# PEACM1.net
KiCad netlist of a schematic drawn in EAGLE
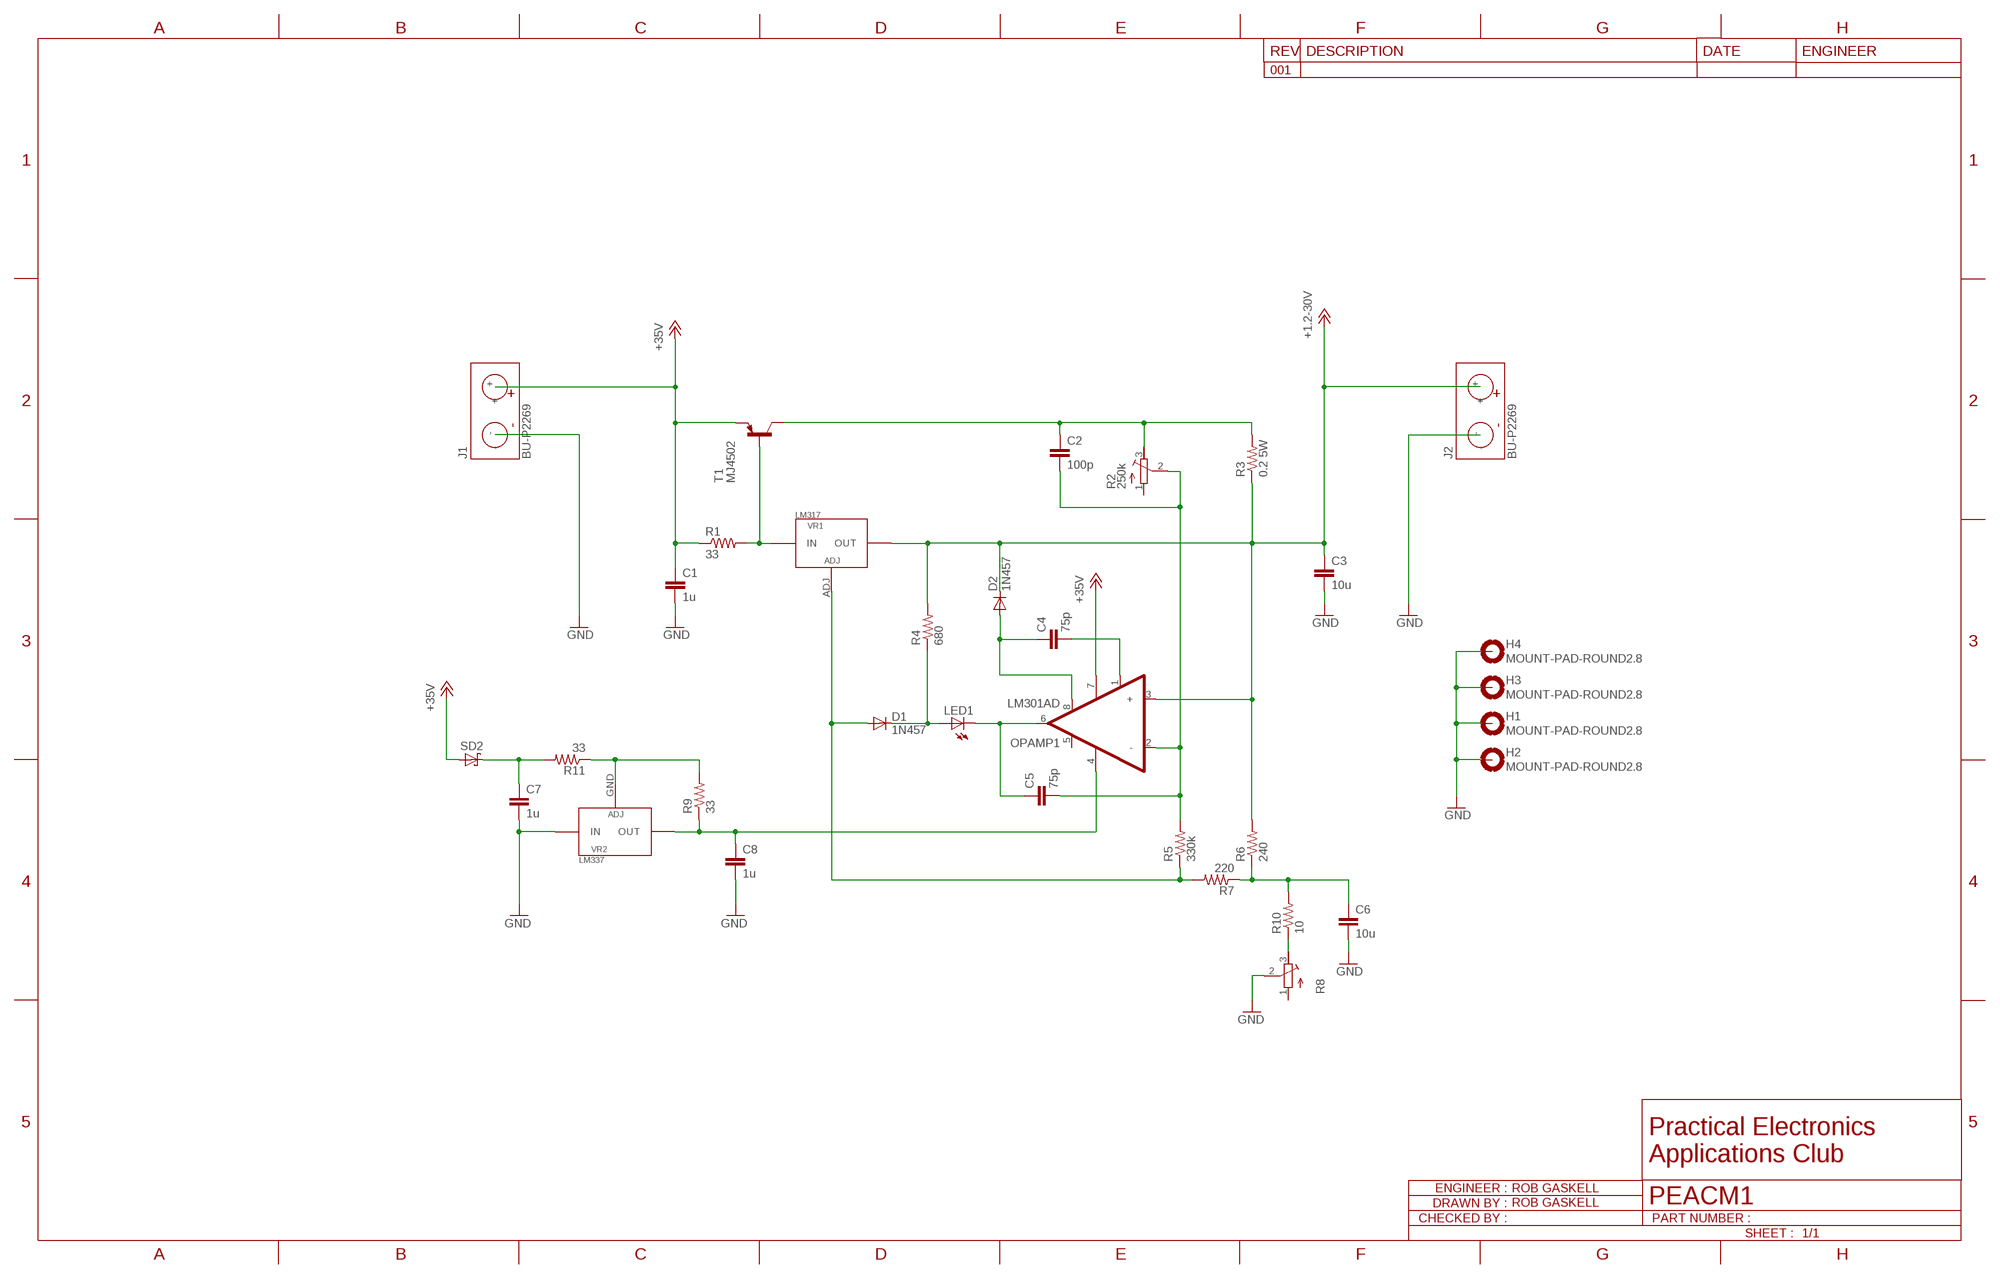
[diagram p0: schematic, sheet 1]

(export (version "E")
  (design (tool "Eeschema 10.0.6"))
  (components
    (comp (ref "C1")
      (value "1u")
      (footprint "eagle-import:C0805")
      (libsource (lib "eagle-import") (part "C-EUC0805"))
    )
    (comp (ref "C2")
      (value "100p")
      (footprint "eagle-import:C0805")
      (libsource (lib "eagle-import") (part "C-EUC0805"))
    )
    (comp (ref "C3")
      (value "10u")
      (footprint "eagle-import:C0805")
      (libsource (lib "eagle-import") (part "C-EUC0805"))
    )
    (comp (ref "C4")
      (value "75p")
      (footprint "eagle-import:C0805")
      (libsource (lib "eagle-import") (part "C-EUC0805"))
    )
    (comp (ref "C5")
      (value "75p")
      (footprint "eagle-import:C0805")
      (libsource (lib "eagle-import") (part "C-EUC0805"))
    )
    (comp (ref "C6")
      (value "10u")
      (footprint "eagle-import:C0805")
      (libsource (lib "eagle-import") (part "C-EUC0805"))
    )
    (comp (ref "C7")
      (value "1u")
      (footprint "eagle-import:C0805")
      (libsource (lib "eagle-import") (part "C-EUC0805"))
    )
    (comp (ref "C8")
      (value "1u")
      (footprint "eagle-import:C0805")
      (libsource (lib "eagle-import") (part "C-EUC0805"))
    )
    (comp (ref "D1")
      (value "1N457")
      (footprint "eagle-import:DO35-10")
      (libsource (lib "eagle-import") (part "DIODE-DO35-10"))
    )
    (comp (ref "D2")
      (value "1N457")
      (footprint "eagle-import:DO35-10")
      (libsource (lib "eagle-import") (part "DIODE-DO35-10"))
    )
    (comp (ref "H1")
      (value "MOUNT-PAD-ROUND2.8")
      (footprint "eagle-import:2,8-PAD")
      (libsource (lib "eagle-import") (part "MOUNT-PAD-ROUND2.8"))
    )
    (comp (ref "H2")
      (value "MOUNT-PAD-ROUND2.8")
      (footprint "eagle-import:2,8-PAD")
      (libsource (lib "eagle-import") (part "MOUNT-PAD-ROUND2.8"))
    )
    (comp (ref "H3")
      (value "MOUNT-PAD-ROUND2.8")
      (footprint "eagle-import:2,8-PAD")
      (libsource (lib "eagle-import") (part "MOUNT-PAD-ROUND2.8"))
    )
    (comp (ref "H4")
      (value "MOUNT-PAD-ROUND2.8")
      (footprint "eagle-import:2,8-PAD")
      (libsource (lib "eagle-import") (part "MOUNT-PAD-ROUND2.8"))
    )
    (comp (ref "J1")
      (value "BU-P2269")
      (footprint "eagle-import:BU-P2269")
      (libsource (lib "eagle-import") (part "BU-P2269"))
    )
    (comp (ref "J2")
      (value "BU-P2269")
      (footprint "eagle-import:BU-P2269")
      (libsource (lib "eagle-import") (part "BU-P2269"))
    )
    (comp (ref "LED1")
      (value "LEDCHIPLED_1206")
      (footprint "eagle-import:CHIPLED_1206")
      (libsource (lib "eagle-import") (part "LEDCHIPLED_1206"))
    )
    (comp (ref "OPAMP1")
      (value "LM301AD")
      (footprint "eagle-import:SOIC8")
      (libsource (lib "eagle-import") (part "LM301AD"))
    )
    (comp (ref "R1")
      (value "33")
      (footprint "eagle-import:M1206")
      (libsource (lib "eagle-import") (part "R-US_M1206"))
    )
    (comp (ref "R2")
      (value "250k")
      (footprint "eagle-import:RTRIM4G_J")
      (libsource (lib "eagle-import") (part "R-TRIMM4G/J"))
    )
    (comp (ref "R3")
      (value "0.2 5W")
      (footprint "eagle-import:R4527")
      (libsource (lib "eagle-import") (part "R-US_R4527"))
    )
    (comp (ref "R4")
      (value "680")
      (footprint "eagle-import:M1206")
      (libsource (lib "eagle-import") (part "R-US_M1206"))
    )
    (comp (ref "R5")
      (value "330k")
      (footprint "eagle-import:M1206")
      (libsource (lib "eagle-import") (part "R-US_M1206"))
    )
    (comp (ref "R6")
      (value "240")
      (footprint "eagle-import:R1206")
      (libsource (lib "eagle-import") (part "R-US_R1206"))
    )
    (comp (ref "R7")
      (value "220")
      (footprint "eagle-import:R1206")
      (libsource (lib "eagle-import") (part "R-US_R1206"))
    )
    (comp (ref "R8")
      (value "R-TRIMM4G/J")
      (footprint "eagle-import:RTRIM4G_J")
      (libsource (lib "eagle-import") (part "R-TRIMM4G/J"))
    )
    (comp (ref "R9")
      (value "33")
      (footprint "eagle-import:M1206")
      (libsource (lib "eagle-import") (part "R-US_M1206"))
    )
    (comp (ref "R10")
      (value "10")
      (footprint "eagle-import:R1206")
      (libsource (lib "eagle-import") (part "R-US_R1206"))
    )
    (comp (ref "R11")
      (value "33")
      (footprint "eagle-import:M1206")
      (libsource (lib "eagle-import") (part "R-US_M1206"))
    )
    (comp (ref "SD2")
      (value "STPS0540Z")
      (footprint "eagle-import:SOD-123")
      (libsource (lib "eagle-import") (part "STPS0540Z"))
    )
    (comp (ref "T1")
      (value "MJ4502")
      (footprint "eagle-import:TO3")
      (libsource (lib "eagle-import") (part "-PNP-TO3"))
    )
    (comp (ref "VR1")
      (value "LM317")
      (footprint "eagle-import:D2PAK-3")
      (libsource (lib "eagle-import") (part "LM317"))
    )
    (comp (ref "VR2")
      (value "LM337")
      (footprint "eagle-import:DPAK(TO-252)")
      (libsource (lib "eagle-import") (part "LM337"))
    )
  )
  (nets
    (net (code "1") (name "+1.2-30V") (class "Default")
      (node (ref "C3") (pin "1") (pinfunction "1_1") (pintype "passive"))
      (node (ref "D2") (pin "C") (pinfunction "C_C") (pintype "passive"))
      (node (ref "J2") (pin "+") (pinfunction "+_+") (pintype "bidirectional"))
      (node (ref "OPAMP1") (pin "3") (pinfunction "+_3") (pintype "input"))
      (node (ref "R3") (pin "1") (pinfunction "1_1") (pintype "passive"))
      (node (ref "R4") (pin "2") (pinfunction "2_2") (pintype "passive"))
      (node (ref "R6") (pin "2") (pinfunction "2_2") (pintype "passive"))
      (node (ref "VR1") (pin "VOUT") (pinfunction "OUT_VOUT") (pintype "passive"))
    )
    (net (code "2") (name "+35V") (class "Default")
      (node (ref "C1") (pin "1") (pinfunction "1_1") (pintype "passive"))
      (node (ref "J1") (pin "+") (pinfunction "+_+") (pintype "bidirectional"))
      (node (ref "OPAMP1") (pin "7") (pinfunction "VCC+_7") (pintype "power_in"))
      (node (ref "R1") (pin "1") (pinfunction "1_1") (pintype "passive"))
      (node (ref "SD2") (pin "A") (pinfunction "A_A") (pintype "passive"))
      (node (ref "T1") (pin "E") (pinfunction "E_E") (pintype "passive"))
    )
    (net (code "3") (name "GND") (class "Default")
      (node (ref "C1") (pin "2") (pinfunction "2_2") (pintype "passive"))
      (node (ref "C3") (pin "2") (pinfunction "2_2") (pintype "passive"))
      (node (ref "C6") (pin "2") (pinfunction "2_2") (pintype "passive"))
      (node (ref "C7") (pin "2") (pinfunction "2_2") (pintype "passive"))
      (node (ref "C8") (pin "2") (pinfunction "2_2") (pintype "passive"))
      (node (ref "H1") (pin "B2,8") (pinfunction "MOUNT_B2,8") (pintype "passive"))
      (node (ref "H2") (pin "B2,8") (pinfunction "MOUNT_B2,8") (pintype "passive"))
      (node (ref "H3") (pin "B2,8") (pinfunction "MOUNT_B2,8") (pintype "passive"))
      (node (ref "H4") (pin "B2,8") (pinfunction "MOUNT_B2,8") (pintype "passive"))
      (node (ref "J1") (pin "-") (pinfunction "-_-") (pintype "bidirectional"))
      (node (ref "J2") (pin "-") (pinfunction "-_-") (pintype "bidirectional"))
      (node (ref "R8") (pin "2") (pinfunction "S_2") (pintype "passive"))
      (node (ref "VR2") (pin "INPUT") (pinfunction "IN_INPUT") (pintype "passive"))
    )
    (net (code "4") (name "Net-(C4-Pad1)") (class "Default")
      (node (ref "C4") (pin "1") (pinfunction "1_1") (pintype "passive"))
      (node (ref "D2") (pin "A") (pinfunction "A_A") (pintype "passive"))
      (node (ref "OPAMP1") (pin "8") (pinfunction "BAL_8") (pintype "bidirectional"))
    )
    (net (code "5") (name "Net-(C6-Pad1)") (class "Default")
      (node (ref "C6") (pin "1") (pinfunction "1_1") (pintype "passive"))
      (node (ref "R10") (pin "2") (pinfunction "2_2") (pintype "passive"))
      (node (ref "R6") (pin "1") (pinfunction "1_1") (pintype "passive"))
      (node (ref "R7") (pin "1") (pinfunction "1_1") (pintype "passive"))
    )
    (net (code "6") (name "Net-(C7-Pad1)") (class "Default")
      (node (ref "C7") (pin "1") (pinfunction "1_1") (pintype "passive"))
      (node (ref "R11") (pin "2") (pinfunction "2_2") (pintype "passive"))
      (node (ref "SD2") (pin "C") (pinfunction "C_C") (pintype "passive"))
    )
    (net (code "7") (name "Net-(D1-PadA)") (class "Default")
      (node (ref "D1") (pin "A") (pinfunction "A_A") (pintype "passive"))
      (node (ref "R5") (pin "1") (pinfunction "1_1") (pintype "passive"))
      (node (ref "R7") (pin "2") (pinfunction "2_2") (pintype "passive"))
      (node (ref "VR1") (pin "ADJ") (pinfunction "ADJ_ADJ") (pintype "passive"))
    )
    (net (code "8") (name "Net-(D1-PadC)") (class "Default")
      (node (ref "D1") (pin "C") (pinfunction "C_C") (pintype "passive"))
      (node (ref "LED1") (pin "A") (pinfunction "A_A") (pintype "passive"))
      (node (ref "R4") (pin "1") (pinfunction "1_1") (pintype "passive"))
    )
    (net (code "9") (name "Net-(OPAMP1--)") (class "Default")
      (node (ref "C2") (pin "2") (pinfunction "2_2") (pintype "passive"))
      (node (ref "C5") (pin "2") (pinfunction "2_2") (pintype "passive"))
      (node (ref "OPAMP1") (pin "2") (pinfunction "-_2") (pintype "input"))
      (node (ref "R2") (pin "2") (pinfunction "S_2") (pintype "passive"))
      (node (ref "R5") (pin "2") (pinfunction "2_2") (pintype "passive"))
    )
    (net (code "10") (name "Net-(OPAMP1-BAL#1)") (class "Default")
      (node (ref "C4") (pin "2") (pinfunction "2_2") (pintype "passive"))
      (node (ref "OPAMP1") (pin "1") (pinfunction "BAL#1_1") (pintype "bidirectional"))
    )
    (net (code "11") (name "Net-(OPAMP1-OUT_A)") (class "Default")
      (node (ref "C5") (pin "1") (pinfunction "1_1") (pintype "passive"))
      (node (ref "LED1") (pin "C") (pinfunction "C_C") (pintype "passive"))
      (node (ref "OPAMP1") (pin "6") (pinfunction "OUT_A_6") (pintype "output"))
    )
    (net (code "12") (name "Net-(OPAMP1-VCC-)") (class "Default")
      (node (ref "C8") (pin "1") (pinfunction "1_1") (pintype "passive"))
      (node (ref "OPAMP1") (pin "4") (pinfunction "VCC-_4") (pintype "power_in"))
      (node (ref "R9") (pin "1") (pinfunction "1_1") (pintype "passive"))
      (node (ref "VR2") (pin "OUTPUT") (pinfunction "OUT_OUTPUT") (pintype "passive"))
    )
    (net (code "13") (name "Net-(R2-E)") (class "Default")
      (node (ref "C2") (pin "1") (pinfunction "1_1") (pintype "passive"))
      (node (ref "R2") (pin "3") (pinfunction "E_3") (pintype "passive"))
      (node (ref "R3") (pin "2") (pinfunction "2_2") (pintype "passive"))
      (node (ref "T1") (pin "C") (pinfunction "C_C") (pintype "passive"))
    )
    (net (code "14") (name "Net-(R8-E)") (class "Default")
      (node (ref "R10") (pin "1") (pinfunction "1_1") (pintype "passive"))
      (node (ref "R8") (pin "3") (pinfunction "E_3") (pintype "passive"))
    )
    (net (code "15") (name "Net-(VR1-IN)") (class "Default")
      (node (ref "R1") (pin "2") (pinfunction "2_2") (pintype "passive"))
      (node (ref "T1") (pin "B") (pinfunction "B_B") (pintype "passive"))
      (node (ref "VR1") (pin "VIN") (pinfunction "IN_VIN") (pintype "passive"))
    )
    (net (code "16") (name "Net-(VR2-ADJ)") (class "Default")
      (node (ref "R11") (pin "1") (pinfunction "1_1") (pintype "passive"))
      (node (ref "R9") (pin "2") (pinfunction "2_2") (pintype "passive"))
      (node (ref "VR2") (pin "GND") (pinfunction "ADJ_GND") (pintype "passive"))
    )
    (net (code "17") (name "unconnected-(OPAMP1-BAL-Pad5)") (class "Default")
      (node (ref "OPAMP1") (pin "5") (pinfunction "BAL_5") (pintype "bidirectional"))
    )
    (net (code "18") (name "unconnected-(R2-A-Pad1)") (class "Default")
      (node (ref "R2") (pin "1") (pinfunction "A_1") (pintype "passive"))
    )
    (net (code "19") (name "unconnected-(R8-A-Pad1)") (class "Default")
      (node (ref "R8") (pin "1") (pinfunction "A_1") (pintype "passive"))
    )
  )
)
